# 5_step_seq.net
KiCad netlist of a schematic drawn in Altium Designer
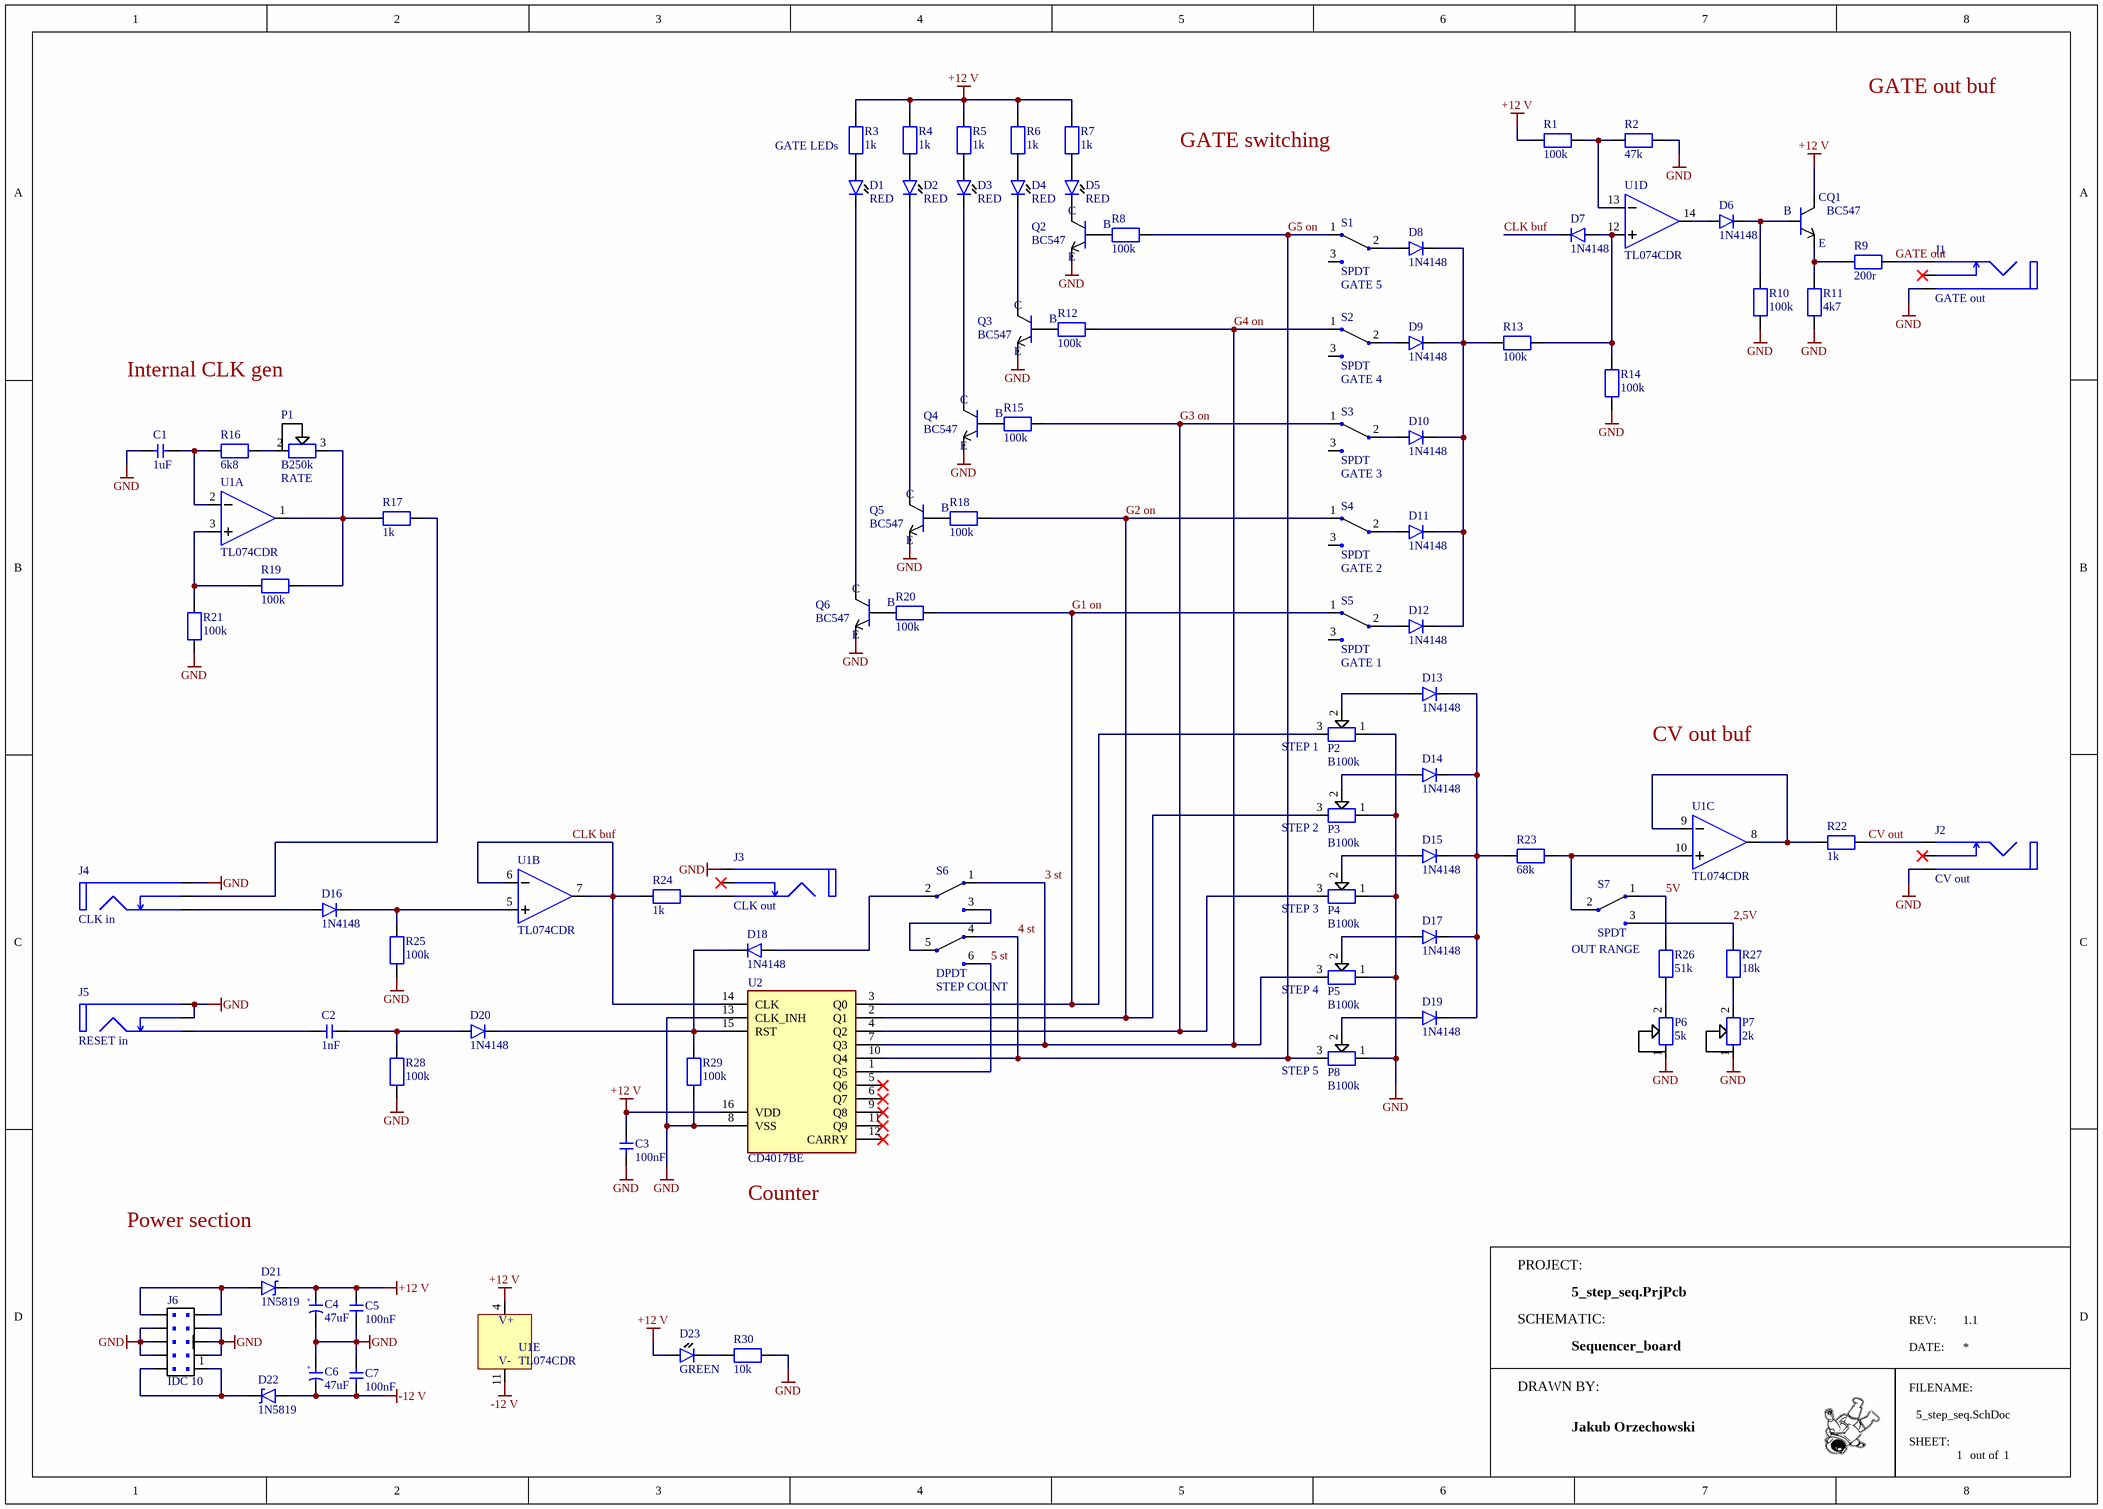
[diagram p0: 5_step_seq.SchDoc]

(export (version "E")
  (design (tool "Eeschema 10.0.6"))
  (components
    (comp (ref "C1")
      (value "1uF")
      (footprint "Cap THT 5mm")
      (description "THT Capacitor Non-Polarised 5 mm Pitch")
      (fields (field (name "Comment") "CAP"))
      (libsource (lib "Generic components") (part "Capacitor THT 5mm"))
    )
    (comp (ref "C2")
      (value "1nF")
      (footprint "Cap THT 5mm")
      (description "THT Capacitor Non-Polarised 5 mm Pitch")
      (fields (field (name "Comment") "CAP"))
      (libsource (lib "Generic components") (part "Capacitor THT 5mm"))
    )
    (comp (ref "C3")
      (value "100nF")
      (footprint "Cap THT 5mm")
      (description "THT Capacitor Non-Polarised 5 mm Pitch")
      (fields (field (name "Comment") "CAP"))
      (libsource (lib "Generic components") (part "Capacitor THT 5mm"))
    )
    (comp (ref "C4")
      (value "47uF")
      (footprint "Cap electrolytic THT 5mm")
      (description "THT Electrolytic Capacitor 5 mm Diameter")
      (fields (field (name "Comment") "CAP"))
      (libsource (lib "Generic components") (part "Capacitor Electr THT 5mm"))
    )
    (comp (ref "C5")
      (value "100nF")
      (footprint "Cap THT 5mm")
      (description "THT Capacitor Non-Polarised 5 mm Pitch")
      (fields (field (name "Comment") "CAP"))
      (libsource (lib "Generic components") (part "Capacitor THT 5mm"))
    )
    (comp (ref "C6")
      (value "47uF")
      (footprint "Cap electrolytic THT 5mm")
      (description "THT Electrolytic Capacitor 5 mm Diameter")
      (fields (field (name "Comment") "CAP"))
      (libsource (lib "Generic components") (part "Capacitor Electr THT 5mm"))
    )
    (comp (ref "C7")
      (value "100nF")
      (footprint "Cap THT 5mm")
      (description "THT Capacitor Non-Polarised 5 mm Pitch")
      (fields (field (name "Comment") "CAP"))
      (libsource (lib "Generic components") (part "Capacitor THT 5mm"))
    )
    (comp (ref "D1")
      (value "LED")
      (footprint "LED THT 5 mm raised")
      (description "THT LED Diode 5 mm Diameter")
      (fields (field (name "COLOR") "RED"))
      (libsource (lib "Opto") (part "LED THT"))
    )
    (comp (ref "D2")
      (value "LED")
      (footprint "LED THT 5 mm raised")
      (description "THT LED Diode 5 mm Diameter")
      (fields (field (name "COLOR") "RED"))
      (libsource (lib "Opto") (part "LED THT"))
    )
    (comp (ref "D3")
      (value "LED")
      (footprint "LED THT 5 mm raised")
      (description "THT LED Diode 5 mm Diameter")
      (fields (field (name "COLOR") "RED"))
      (libsource (lib "Opto") (part "LED THT"))
    )
    (comp (ref "D4")
      (value "LED")
      (footprint "LED THT 5 mm raised")
      (description "THT LED Diode 5 mm Diameter")
      (fields (field (name "COLOR") "RED"))
      (libsource (lib "Opto") (part "LED THT"))
    )
    (comp (ref "D5")
      (value "LED")
      (footprint "LED THT 5 mm raised")
      (description "THT LED Diode 5 mm Diameter")
      (fields (field (name "COLOR") "RED"))
      (libsource (lib "Opto") (part "LED THT"))
    )
    (comp (ref "D6")
      (value "DIODE")
      (footprint "Diode THT 10 mm")
      (description "Generic THT Axial Diode 10 mm Pitch")
      (fields (field (name "MODEL") "1N4148"))
      (libsource (lib "Diodes") (part "Diode THT"))
    )
    (comp (ref "D7")
      (value "DIODE")
      (footprint "Diode THT 10 mm")
      (description "Generic THT Axial Diode 10 mm Pitch")
      (fields (field (name "MODEL") "1N4148"))
      (libsource (lib "Diodes") (part "Diode THT"))
    )
    (comp (ref "D8")
      (value "DIODE")
      (footprint "Diode THT 10 mm")
      (description "Generic THT Axial Diode 10 mm Pitch")
      (fields (field (name "MODEL") "1N4148"))
      (libsource (lib "Diodes") (part "Diode THT"))
    )
    (comp (ref "D9")
      (value "DIODE")
      (footprint "Diode THT 10 mm")
      (description "Generic THT Axial Diode 10 mm Pitch")
      (fields (field (name "MODEL") "1N4148"))
      (libsource (lib "Diodes") (part "Diode THT"))
    )
    (comp (ref "D10")
      (value "DIODE")
      (footprint "Diode THT 10 mm")
      (description "Generic THT Axial Diode 10 mm Pitch")
      (fields (field (name "MODEL") "1N4148"))
      (libsource (lib "Diodes") (part "Diode THT"))
    )
    (comp (ref "D11")
      (value "DIODE")
      (footprint "Diode THT 10 mm")
      (description "Generic THT Axial Diode 10 mm Pitch")
      (fields (field (name "MODEL") "1N4148"))
      (libsource (lib "Diodes") (part "Diode THT"))
    )
    (comp (ref "D12")
      (value "DIODE")
      (footprint "Diode THT 10 mm")
      (description "Generic THT Axial Diode 10 mm Pitch")
      (fields (field (name "MODEL") "1N4148"))
      (libsource (lib "Diodes") (part "Diode THT"))
    )
    (comp (ref "D13")
      (value "DIODE")
      (footprint "Diode THT 10 mm")
      (description "Generic THT Axial Diode 10 mm Pitch")
      (fields (field (name "MODEL") "1N4148"))
      (libsource (lib "Diodes") (part "Diode THT"))
    )
    (comp (ref "D14")
      (value "DIODE")
      (footprint "Diode THT 10 mm")
      (description "Generic THT Axial Diode 10 mm Pitch")
      (fields (field (name "MODEL") "1N4148"))
      (libsource (lib "Diodes") (part "Diode THT"))
    )
    (comp (ref "D15")
      (value "DIODE")
      (footprint "Diode THT 10 mm")
      (description "Generic THT Axial Diode 10 mm Pitch")
      (fields (field (name "MODEL") "1N4148"))
      (libsource (lib "Diodes") (part "Diode THT"))
    )
    (comp (ref "D16")
      (value "DIODE")
      (footprint "Diode THT 10 mm")
      (description "Generic THT Axial Diode 10 mm Pitch")
      (fields (field (name "MODEL") "1N4148"))
      (libsource (lib "Diodes") (part "Diode THT"))
    )
    (comp (ref "D17")
      (value "DIODE")
      (footprint "Diode THT 10 mm")
      (description "Generic THT Axial Diode 10 mm Pitch")
      (fields (field (name "MODEL") "1N4148"))
      (libsource (lib "Diodes") (part "Diode THT"))
    )
    (comp (ref "D18")
      (value "DIODE")
      (footprint "Diode THT 10 mm")
      (description "Generic THT Axial Diode 10 mm Pitch")
      (fields (field (name "MODEL") "1N4148"))
      (libsource (lib "Diodes") (part "Diode THT"))
    )
    (comp (ref "D19")
      (value "DIODE")
      (footprint "Diode THT 10 mm")
      (description "Generic THT Axial Diode 10 mm Pitch")
      (fields (field (name "MODEL") "1N4148"))
      (libsource (lib "Diodes") (part "Diode THT"))
    )
    (comp (ref "D20")
      (value "DIODE")
      (footprint "Diode THT 10 mm")
      (description "Generic THT Axial Diode 10 mm Pitch")
      (fields (field (name "MODEL") "1N4148"))
      (libsource (lib "Diodes") (part "Diode THT"))
    )
    (comp (ref "D21")
      (value "SCHOTTKY")
      (footprint "Diode THT 10 mm")
      (description "Generic THT Axial Schottky Diode 10 mm Pitch")
      (fields (field (name "MODEL") "1N5819"))
      (libsource (lib "Diodes") (part "Schottky Diode THT"))
    )
    (comp (ref "D22")
      (value "SCHOTTKY")
      (footprint "Diode THT 10 mm")
      (description "Generic THT Axial Schottky Diode 10 mm Pitch")
      (fields (field (name "MODEL") "1N5819"))
      (libsource (lib "Diodes") (part "Schottky Diode THT"))
    )
    (comp (ref "D23")
      (value "LED")
      (footprint "LED SMD 0805")
      (description "SMD LED Diode 0805 Package")
      (fields (field (name "COLOR") "GREEN"))
      (libsource (lib "Opto") (part "LED SMD"))
    )
    (comp (ref "J1")
      (value "JACK Mono")
      (footprint "PJ301M")
      (description "PJ301M Eurorack 3,5 mm Patch Socket PCB Mount")
      (fields (field (name "LABEL") "GATE out"))
      (libsource (lib "Connectors") (part "PJ301M"))
    )
    (comp (ref "J2")
      (value "JACK Mono")
      (footprint "PJ301M")
      (description "PJ301M Eurorack 3,5 mm Patch Socket PCB Mount")
      (fields (field (name "LABEL") "CV out"))
      (libsource (lib "Connectors") (part "PJ301M"))
    )
    (comp (ref "J3")
      (value "JACK Mono")
      (footprint "PJ301M")
      (description "PJ301M Eurorack 3,5 mm Patch Socket PCB Mount")
      (fields (field (name "LABEL") "CLK out"))
      (libsource (lib "Connectors") (part "PJ301M"))
    )
    (comp (ref "J4")
      (value "JACK Mono")
      (footprint "PJ301M")
      (description "PJ301M Eurorack 3,5 mm Patch Socket PCB Mount")
      (fields (field (name "LABEL") "CLK in"))
      (libsource (lib "Connectors") (part "PJ301M"))
    )
    (comp (ref "J5")
      (value "JACK Mono")
      (footprint "PJ301M")
      (description "PJ301M Eurorack 3,5 mm Patch Socket PCB Mount")
      (fields (field (name "LABEL") "RESET in"))
      (libsource (lib "Connectors") (part "PJ301M"))
    )
    (comp (ref "J6")
      (value "IDC 10")
      (footprint "IDC 10 PIN")
      (description "10 Pin IDC Connector")
      (libsource (lib "Connectors") (part "IDC 10 pin"))
    )
    (comp (ref "P1")
      (value "B250k")
      (footprint "9 mm PCB Potentiometer")
      (description "PCB Mount 9mm Mono Potentiometer THT as Variable Resistor Clockwise Decrease")
      (fields (field (name "PARAMETER") "RATE") (field (name "Comment") "VR"))
      (libsource (lib "Potentiometers") (part "VR B 9 mm"))
    )
    (comp (ref "P2")
      (value "B100k")
      (footprint "9 mm PCB Potentiometer")
      (description "PCB Mount 9mm Mono Potentiometer THT")
      (fields (field (name "PARAMETER") "STEP 1") (field (name "Comment") "Mono Pot"))
      (libsource (lib "Potentiometers") (part "Potentiometer 9 mm"))
    )
    (comp (ref "P3")
      (value "B100k")
      (footprint "9 mm PCB Potentiometer")
      (description "PCB Mount 9mm Mono Potentiometer THT")
      (fields (field (name "PARAMETER") "STEP 2") (field (name "Comment") "Mono Pot"))
      (libsource (lib "Potentiometers") (part "Potentiometer 9 mm"))
    )
    (comp (ref "P4")
      (value "B100k")
      (footprint "9 mm PCB Potentiometer")
      (description "PCB Mount 9mm Mono Potentiometer THT")
      (fields (field (name "PARAMETER") "STEP 3") (field (name "Comment") "Mono Pot"))
      (libsource (lib "Potentiometers") (part "Potentiometer 9 mm"))
    )
    (comp (ref "P5")
      (value "B100k")
      (footprint "9 mm PCB Potentiometer")
      (description "PCB Mount 9mm Mono Potentiometer THT")
      (fields (field (name "PARAMETER") "STEP 4") (field (name "Comment") "Mono Pot"))
      (libsource (lib "Potentiometers") (part "Potentiometer 9 mm"))
    )
    (comp (ref "P6")
      (value "5k")
      (footprint "Multiturn Potentiometer inline")
      (description "PCB Mount Multiturn Trimmer Potentiometer Top Adjustable as Variable Resistor Clockwise Increase")
      (fields (field (name "Comment") "VR"))
      (libsource (lib "Potentiometers") (part "VR A Multiturn THT"))
    )
    (comp (ref "P7")
      (value "2k")
      (footprint "Multiturn Potentiometer inline")
      (description "PCB Mount Multiturn Trimmer Potentiometer Top Adjustable as Variable Resistor Clockwise Increase")
      (fields (field (name "Comment") "VR"))
      (libsource (lib "Potentiometers") (part "VR A Multiturn THT"))
    )
    (comp (ref "P8")
      (value "B100k")
      (footprint "9 mm PCB Potentiometer")
      (description "PCB Mount 9mm Mono Potentiometer THT")
      (fields (field (name "PARAMETER") "STEP 5") (field (name "Comment") "Mono Pot"))
      (libsource (lib "Potentiometers") (part "Potentiometer 9 mm"))
    )
    (comp (ref "Q1")
      (value "BC547")
      (footprint "TO-92 wide")
      (description "BC547 NPN Transistor THT TO-92 Package")
      (libsource (lib "Transistors") (part "BC547"))
    )
    (comp (ref "Q2")
      (value "BC547")
      (footprint "TO-92 wide")
      (description "BC547 NPN Transistor THT TO-92 Package")
      (libsource (lib "Transistors") (part "BC547"))
    )
    (comp (ref "Q3")
      (value "BC547")
      (footprint "TO-92 wide")
      (description "BC547 NPN Transistor THT TO-92 Package")
      (libsource (lib "Transistors") (part "BC547"))
    )
    (comp (ref "Q4")
      (value "BC547")
      (footprint "TO-92 wide")
      (description "BC547 NPN Transistor THT TO-92 Package")
      (libsource (lib "Transistors") (part "BC547"))
    )
    (comp (ref "Q5")
      (value "BC547")
      (footprint "TO-92 wide")
      (description "BC547 NPN Transistor THT TO-92 Package")
      (libsource (lib "Transistors") (part "BC547"))
    )
    (comp (ref "Q6")
      (value "BC547")
      (footprint "TO-92 wide")
      (description "BC547 NPN Transistor THT TO-92 Package")
      (libsource (lib "Transistors") (part "BC547"))
    )
    (comp (ref "R1")
      (value "100k")
      (footprint "Resistor THT vertical")
      (description "THT Axial Resistor 10mm Pitch")
      (fields (field (name "Comment") "RES"))
      (libsource (lib "Generic components") (part "Resistor THT"))
    )
    (comp (ref "R2")
      (value "47k")
      (footprint "Resistor THT vertical")
      (description "THT Axial Resistor 10mm Pitch")
      (fields (field (name "Comment") "RES"))
      (libsource (lib "Generic components") (part "Resistor THT"))
    )
    (comp (ref "R3")
      (value "1k")
      (footprint "Resistor THT vertical")
      (description "THT Axial Resistor 10mm Pitch")
      (fields (field (name "Comment") "RES"))
      (libsource (lib "Generic components") (part "Resistor THT"))
    )
    (comp (ref "R4")
      (value "1k")
      (footprint "Resistor THT vertical")
      (description "THT Axial Resistor 10mm Pitch")
      (fields (field (name "Comment") "RES"))
      (libsource (lib "Generic components") (part "Resistor THT"))
    )
    (comp (ref "R5")
      (value "1k")
      (footprint "Resistor THT vertical")
      (description "THT Axial Resistor 10mm Pitch")
      (fields (field (name "Comment") "RES"))
      (libsource (lib "Generic components") (part "Resistor THT"))
    )
    (comp (ref "R6")
      (value "1k")
      (footprint "Resistor THT vertical")
      (description "THT Axial Resistor 10mm Pitch")
      (fields (field (name "Comment") "RES"))
      (libsource (lib "Generic components") (part "Resistor THT"))
    )
    (comp (ref "R7")
      (value "1k")
      (footprint "Resistor THT vertical")
      (description "THT Axial Resistor 10mm Pitch")
      (fields (field (name "Comment") "RES"))
      (libsource (lib "Generic components") (part "Resistor THT"))
    )
    (comp (ref "R8")
      (value "100k")
      (footprint "Resistor THT 10mm")
      (description "THT Axial Resistor 10mm Pitch")
      (fields (field (name "Comment") "RES"))
      (libsource (lib "Generic components") (part "Resistor THT"))
    )
    (comp (ref "R9")
      (value "200r")
      (footprint "Resistor THT vertical")
      (description "THT Axial Resistor 10mm Pitch")
      (fields (field (name "Comment") "RES"))
      (libsource (lib "Generic components") (part "Resistor THT"))
    )
    (comp (ref "R10")
      (value "100k")
      (footprint "Resistor THT vertical")
      (description "THT Axial Resistor 10mm Pitch")
      (fields (field (name "Comment") "RES"))
      (libsource (lib "Generic components") (part "Resistor THT"))
    )
    (comp (ref "R11")
      (value "4k7")
      (footprint "Resistor THT vertical")
      (description "THT Axial Resistor 10mm Pitch")
      (fields (field (name "Comment") "RES"))
      (libsource (lib "Generic components") (part "Resistor THT"))
    )
    (comp (ref "R12")
      (value "100k")
      (footprint "Resistor THT 10mm")
      (description "THT Axial Resistor 10mm Pitch")
      (fields (field (name "Comment") "RES"))
      (libsource (lib "Generic components") (part "Resistor THT"))
    )
    (comp (ref "R13")
      (value "100k")
      (footprint "Resistor THT vertical")
      (description "THT Axial Resistor 10mm Pitch")
      (fields (field (name "Comment") "RES"))
      (libsource (lib "Generic components") (part "Resistor THT"))
    )
    (comp (ref "R14")
      (value "100k")
      (footprint "Resistor THT vertical")
      (description "THT Axial Resistor 10mm Pitch")
      (fields (field (name "Comment") "RES"))
      (libsource (lib "Generic components") (part "Resistor THT"))
    )
    (comp (ref "R15")
      (value "100k")
      (footprint "Resistor THT 10mm")
      (description "THT Axial Resistor 10mm Pitch")
      (fields (field (name "Comment") "RES"))
      (libsource (lib "Generic components") (part "Resistor THT"))
    )
    (comp (ref "R16")
      (value "6k8")
      (footprint "Resistor THT 10mm")
      (description "THT Axial Resistor 10mm Pitch")
      (fields (field (name "Comment") "RES"))
      (libsource (lib "Generic components") (part "Resistor THT"))
    )
    (comp (ref "R17")
      (value "1k")
      (footprint "Resistor THT 10mm")
      (description "THT Axial Resistor 10mm Pitch")
      (fields (field (name "Comment") "RES"))
      (libsource (lib "Generic components") (part "Resistor THT"))
    )
    (comp (ref "R18")
      (value "100k")
      (footprint "Resistor THT 10mm")
      (description "THT Axial Resistor 10mm Pitch")
      (fields (field (name "Comment") "RES"))
      (libsource (lib "Generic components") (part "Resistor THT"))
    )
    (comp (ref "R19")
      (value "100k")
      (footprint "Resistor THT 10mm")
      (description "THT Axial Resistor 10mm Pitch")
      (fields (field (name "Comment") "RES"))
      (libsource (lib "Generic components") (part "Resistor THT"))
    )
    (comp (ref "R20")
      (value "100k")
      (footprint "Resistor THT 10mm")
      (description "THT Axial Resistor 10mm Pitch")
      (fields (field (name "Comment") "RES"))
      (libsource (lib "Generic components") (part "Resistor THT"))
    )
    (comp (ref "R21")
      (value "100k")
      (footprint "Resistor THT 10mm")
      (description "THT Axial Resistor 10mm Pitch")
      (fields (field (name "Comment") "RES"))
      (libsource (lib "Generic components") (part "Resistor THT"))
    )
    (comp (ref "R22")
      (value "1k")
      (footprint "Resistor THT 10mm")
      (description "THT Axial Resistor 10mm Pitch")
      (fields (field (name "Comment") "RES"))
      (libsource (lib "Generic components") (part "Resistor THT"))
    )
    (comp (ref "R23")
      (value "68k")
      (footprint "Resistor THT 10mm")
      (description "THT Axial Resistor 10mm Pitch")
      (fields (field (name "Comment") "RES"))
      (libsource (lib "Generic components") (part "Resistor THT"))
    )
    (comp (ref "R24")
      (value "1k")
      (footprint "Resistor THT vertical")
      (description "THT Axial Resistor 10mm Pitch")
      (fields (field (name "Comment") "RES"))
      (libsource (lib "Generic components") (part "Resistor THT"))
    )
    (comp (ref "R25")
      (value "100k")
      (footprint "Resistor THT 10mm")
      (description "THT Axial Resistor 10mm Pitch")
      (fields (field (name "Comment") "RES"))
      (libsource (lib "Generic components") (part "Resistor THT"))
    )
    (comp (ref "R26")
      (value "51k")
      (footprint "Resistor THT vertical")
      (description "THT Axial Resistor 10mm Pitch")
      (fields (field (name "Comment") "RES"))
      (libsource (lib "Generic components") (part "Resistor THT"))
    )
    (comp (ref "R27")
      (value "18k")
      (footprint "Resistor THT vertical")
      (description "THT Axial Resistor 10mm Pitch")
      (fields (field (name "Comment") "RES"))
      (libsource (lib "Generic components") (part "Resistor THT"))
    )
    (comp (ref "R28")
      (value "100k")
      (footprint "Resistor THT 10mm")
      (description "THT Axial Resistor 10mm Pitch")
      (fields (field (name "Comment") "RES"))
      (libsource (lib "Generic components") (part "Resistor THT"))
    )
    (comp (ref "R29")
      (value "100k")
      (footprint "Resistor THT 10mm")
      (description "THT Axial Resistor 10mm Pitch")
      (fields (field (name "Comment") "RES"))
      (libsource (lib "Generic components") (part "Resistor THT"))
    )
    (comp (ref "R30")
      (value "10k")
      (footprint "Resistor SMD 0805")
      (description "SMD Resistor 0805 package")
      (fields (field (name "Comment") "RES"))
      (libsource (lib "Generic components") (part "Resistor SMD 0805"))
    )
    (comp (ref "S1")
      (value "SPDT")
      (footprint "2MS1T1B5M2RE")
      (description "Single Pole Double Throw on-on Switch")
      (fields (field (name "SIGNALS") "GATE 5"))
      (libsource (lib "Switches") (part "2MS1T1B5M2RE SPDT (Eurorack)"))
    )
    (comp (ref "S2")
      (value "SPDT")
      (footprint "2MS1T1B5M2RE")
      (description "Single Pole Double Throw on-on Switch")
      (fields (field (name "SIGNALS") "GATE 4"))
      (libsource (lib "Switches") (part "2MS1T1B5M2RE SPDT (Eurorack)"))
    )
    (comp (ref "S3")
      (value "SPDT")
      (footprint "2MS1T1B5M2RE")
      (description "Single Pole Double Throw on-on Switch")
      (fields (field (name "SIGNALS") "GATE 3"))
      (libsource (lib "Switches") (part "2MS1T1B5M2RE SPDT (Eurorack)"))
    )
    (comp (ref "S4")
      (value "SPDT")
      (footprint "2MS1T1B5M2RE")
      (description "Single Pole Double Throw on-on Switch")
      (fields (field (name "SIGNALS") "GATE 2"))
      (libsource (lib "Switches") (part "2MS1T1B5M2RE SPDT (Eurorack)"))
    )
    (comp (ref "S5")
      (value "SPDT")
      (footprint "2MS1T1B5M2RE")
      (description "Single Pole Double Throw on-on Switch")
      (fields (field (name "SIGNALS") "GATE 1"))
      (libsource (lib "Switches") (part "2MS1T1B5M2RE SPDT (Eurorack)"))
    )
    (comp (ref "S6")
      (value "DPDT")
      (footprint "2MD6T1B5M2RE")
      (description "Dual Pole Dual Throw on-on-on Switch")
      (fields (field (name "SIGNALS") "STEP COUNT"))
      (libsource (lib "Switches") (part "2MD6T1B5M2RE DPDT (Eurorack)"))
    )
    (comp (ref "S7")
      (value "SPDT")
      (footprint "2MS1T1B5M2RE")
      (description "Single Pole Double Throw on-on Switch")
      (fields (field (name "SIGNALS") "OUT RANGE"))
      (libsource (lib "Switches") (part "2MS1T1B5M2RE SPDT (Eurorack)"))
    )
    (comp (ref "U1")
      (value "TL074CDR")
      (footprint "SOIC14")
      (description "TL074CDR Quad Op-Amp SOIC14 Package")
      (libsource (lib "OpAmps") (part "TL074CDR SOIC14"))
    )
    (comp (ref "U2")
      (value "CD4017BE")
      (footprint "DIP-16 socket")
      (description "CD4017BE CMOS Decade Counter DIP-16 Package")
      (libsource (lib "ICs") (part "CD4017BE DIP-16"))
    )
  )
  (nets
    (net (code "1") (name "+12 V") (class "Default")
      (node (ref "C3") (pin "2") (pintype "passive"))
      (node (ref "C4") (pin "2") (pintype "passive"))
      (node (ref "C5") (pin "2") (pintype "passive"))
      (node (ref "D21") (pin "2") (pintype "passive"))
      (node (ref "D23") (pin "1") (pintype "passive"))
      (node (ref "Q1") (pin "1") (pintype "passive"))
      (node (ref "R1") (pin "1") (pintype "passive"))
      (node (ref "R3") (pin "2") (pintype "passive"))
      (node (ref "R4") (pin "2") (pintype "passive"))
      (node (ref "R5") (pin "2") (pintype "passive"))
      (node (ref "R6") (pin "2") (pintype "passive"))
      (node (ref "R7") (pin "2") (pintype "passive"))
      (node (ref "U1") (pin "4") (pintype "passive"))
      (node (ref "U2") (pin "16") (pinfunction "VDD_16") (pintype "passive"))
    )
    (net (code "2") (name "-12 V") (class "Default")
      (node (ref "C6") (pin "1") (pintype "passive"))
      (node (ref "C7") (pin "1") (pintype "passive"))
      (node (ref "D22") (pin "1") (pintype "passive"))
      (node (ref "U1") (pin "11") (pintype "passive"))
    )
    (net (code "3") (name "/2,5V") (class "Default")
      (node (ref "R27") (pin "1") (pintype "passive"))
      (node (ref "S7") (pin "3") (pintype "passive"))
    )
    (net (code "4") (name "/3 st") (class "Default")
      (node (ref "P5") (pin "3") (pintype "passive"))
      (node (ref "R12") (pin "2") (pintype "passive"))
      (node (ref "S2") (pin "1") (pintype "passive"))
      (node (ref "S6") (pin "1") (pintype "passive"))
      (node (ref "U2") (pin "7") (pinfunction "Q3_7") (pintype "passive"))
    )
    (net (code "5") (name "/4 st") (class "Default")
      (node (ref "P8") (pin "3") (pintype "passive"))
      (node (ref "R8") (pin "2") (pintype "passive"))
      (node (ref "S1") (pin "1") (pintype "passive"))
      (node (ref "S6") (pin "4") (pintype "passive"))
      (node (ref "U2") (pin "10") (pinfunction "Q4_10") (pintype "passive"))
    )
    (net (code "6") (name "/5 st") (class "Default")
      (node (ref "S6") (pin "6") (pintype "passive"))
      (node (ref "U2") (pin "1") (pinfunction "Q5_1") (pintype "passive"))
    )
    (net (code "7") (name "/5V") (class "Default")
      (node (ref "R26") (pin "1") (pintype "passive"))
      (node (ref "S7") (pin "1") (pintype "passive"))
    )
    (net (code "8") (name "/CLK buf") (class "Default")
      (node (ref "D7") (pin "2") (pintype "passive"))
      (node (ref "R24") (pin "2") (pintype "passive"))
      (node (ref "U1") (pin "6") (pintype "passive"))
      (node (ref "U1") (pin "7") (pintype "passive"))
      (node (ref "U2") (pin "14") (pinfunction "CLK_14") (pintype "passive"))
    )
    (net (code "9") (name "/CV out") (class "Default")
      (node (ref "J2") (pin "3") (pintype "passive"))
      (node (ref "R22") (pin "1") (pintype "passive"))
    )
    (net (code "10") (name "/G1 on") (class "Default")
      (node (ref "P2") (pin "3") (pintype "passive"))
      (node (ref "R20") (pin "2") (pintype "passive"))
      (node (ref "S5") (pin "1") (pintype "passive"))
      (node (ref "U2") (pin "3") (pinfunction "Q0_3") (pintype "passive"))
    )
    (net (code "11") (name "/G2 on") (class "Default")
      (node (ref "P3") (pin "3") (pintype "passive"))
      (node (ref "R18") (pin "2") (pintype "passive"))
      (node (ref "S4") (pin "1") (pintype "passive"))
      (node (ref "U2") (pin "2") (pinfunction "Q1_2") (pintype "passive"))
    )
    (net (code "12") (name "/G3 on") (class "Default")
      (node (ref "P4") (pin "3") (pintype "passive"))
      (node (ref "R15") (pin "2") (pintype "passive"))
      (node (ref "S3") (pin "1") (pintype "passive"))
      (node (ref "U2") (pin "4") (pinfunction "Q2_4") (pintype "passive"))
    )
    (net (code "13") (name "/GATE out") (class "Default")
      (node (ref "J1") (pin "3") (pintype "passive"))
      (node (ref "R9") (pin "1") (pintype "passive"))
    )
    (net (code "14") (name "GND") (class "Default")
      (node (ref "C1") (pin "1") (pintype "passive"))
      (node (ref "C3") (pin "1") (pintype "passive"))
      (node (ref "C4") (pin "1") (pintype "passive"))
      (node (ref "C5") (pin "1") (pintype "passive"))
      (node (ref "C6") (pin "2") (pintype "passive"))
      (node (ref "C7") (pin "2") (pintype "passive"))
      (node (ref "J1") (pin "1") (pintype "passive"))
      (node (ref "J2") (pin "1") (pintype "passive"))
      (node (ref "J3") (pin "1") (pintype "passive"))
      (node (ref "J4") (pin "1") (pintype "passive"))
      (node (ref "J5") (pin "1") (pintype "passive"))
      (node (ref "J5") (pin "2") (pintype "passive"))
      (node (ref "J6") (pin "3") (pintype "passive"))
      (node (ref "J6") (pin "4") (pintype "passive"))
      (node (ref "J6") (pin "5") (pintype "passive"))
      (node (ref "J6") (pin "6") (pintype "passive"))
      (node (ref "J6") (pin "7") (pintype "passive"))
      (node (ref "J6") (pin "8") (pintype "passive"))
      (node (ref "P2") (pin "1") (pintype "passive"))
      (node (ref "P3") (pin "1") (pintype "passive"))
      (node (ref "P4") (pin "1") (pintype "passive"))
      (node (ref "P5") (pin "1") (pintype "passive"))
      (node (ref "P6") (pin "1") (pintype "passive"))
      (node (ref "P7") (pin "1") (pintype "passive"))
      (node (ref "P8") (pin "1") (pintype "passive"))
      (node (ref "Q2") (pin "3") (pintype "passive"))
      (node (ref "Q3") (pin "3") (pintype "passive"))
      (node (ref "Q4") (pin "3") (pintype "passive"))
      (node (ref "Q5") (pin "3") (pintype "passive"))
      (node (ref "Q6") (pin "3") (pintype "passive"))
      (node (ref "R10") (pin "2") (pintype "passive"))
      (node (ref "R11") (pin "2") (pintype "passive"))
      (node (ref "R14") (pin "1") (pintype "passive"))
      (node (ref "R2") (pin "2") (pintype "passive"))
      (node (ref "R21") (pin "1") (pintype "passive"))
      (node (ref "R25") (pin "1") (pintype "passive"))
      (node (ref "R28") (pin "1") (pintype "passive"))
      (node (ref "R29") (pin "1") (pintype "passive"))
      (node (ref "R30") (pin "2") (pintype "passive"))
      (node (ref "U2") (pin "13") (pinfunction "CLK_INH_13") (pintype "passive"))
      (node (ref "U2") (pin "8") (pinfunction "VSS_8") (pintype "passive"))
    )
    (net (code "15") (name "Net-(C1-Pad2)") (class "Default")
      (node (ref "C1") (pin "2") (pintype "passive"))
      (node (ref "R16") (pin "1") (pintype "passive"))
      (node (ref "U1") (pin "2") (pintype "passive"))
    )
    (net (code "16") (name "Net-(C2-Pad1)") (class "Default")
      (node (ref "C2") (pin "1") (pintype "passive"))
      (node (ref "J5") (pin "3") (pintype "passive"))
    )
    (net (code "17") (name "Net-(C2-Pad2)") (class "Default")
      (node (ref "C2") (pin "2") (pintype "passive"))
      (node (ref "D20") (pin "1") (pintype "passive"))
      (node (ref "R28") (pin "2") (pintype "passive"))
    )
    (net (code "18") (name "Net-(D1-Pad1)") (class "Default")
      (node (ref "D1") (pin "1") (pintype "passive"))
      (node (ref "R3") (pin "1") (pintype "passive"))
    )
    (net (code "19") (name "Net-(D1-Pad2)") (class "Default")
      (node (ref "D1") (pin "2") (pintype "passive"))
      (node (ref "Q6") (pin "1") (pintype "passive"))
    )
    (net (code "20") (name "Net-(D2-Pad1)") (class "Default")
      (node (ref "D2") (pin "1") (pintype "passive"))
      (node (ref "R4") (pin "1") (pintype "passive"))
    )
    (net (code "21") (name "Net-(D2-Pad2)") (class "Default")
      (node (ref "D2") (pin "2") (pintype "passive"))
      (node (ref "Q5") (pin "1") (pintype "passive"))
    )
    (net (code "22") (name "Net-(D3-Pad1)") (class "Default")
      (node (ref "D3") (pin "1") (pintype "passive"))
      (node (ref "R5") (pin "1") (pintype "passive"))
    )
    (net (code "23") (name "Net-(D3-Pad2)") (class "Default")
      (node (ref "D3") (pin "2") (pintype "passive"))
      (node (ref "Q4") (pin "1") (pintype "passive"))
    )
    (net (code "24") (name "Net-(D4-Pad1)") (class "Default")
      (node (ref "D4") (pin "1") (pintype "passive"))
      (node (ref "R6") (pin "1") (pintype "passive"))
    )
    (net (code "25") (name "Net-(D4-Pad2)") (class "Default")
      (node (ref "D4") (pin "2") (pintype "passive"))
      (node (ref "Q3") (pin "1") (pintype "passive"))
    )
    (net (code "26") (name "Net-(D5-Pad1)") (class "Default")
      (node (ref "D5") (pin "1") (pintype "passive"))
      (node (ref "R7") (pin "1") (pintype "passive"))
    )
    (net (code "27") (name "Net-(D5-Pad2)") (class "Default")
      (node (ref "D5") (pin "2") (pintype "passive"))
      (node (ref "Q2") (pin "1") (pintype "passive"))
    )
    (net (code "28") (name "Net-(D6-Pad1)") (class "Default")
      (node (ref "D6") (pin "1") (pintype "passive"))
      (node (ref "U1") (pin "14") (pintype "passive"))
    )
    (net (code "29") (name "Net-(D6-Pad2)") (class "Default")
      (node (ref "D6") (pin "2") (pintype "passive"))
      (node (ref "Q1") (pin "2") (pintype "passive"))
      (node (ref "R10") (pin "1") (pintype "passive"))
    )
    (net (code "30") (name "Net-(D7-Pad1)") (class "Default")
      (node (ref "D7") (pin "1") (pintype "passive"))
      (node (ref "R13") (pin "2") (pintype "passive"))
      (node (ref "R14") (pin "2") (pintype "passive"))
      (node (ref "U1") (pin "12") (pintype "passive"))
    )
    (net (code "31") (name "Net-(D8-Pad1)") (class "Default")
      (node (ref "D8") (pin "1") (pintype "passive"))
      (node (ref "S1") (pin "2") (pintype "passive"))
    )
    (net (code "32") (name "Net-(D9-Pad1)") (class "Default")
      (node (ref "D9") (pin "1") (pintype "passive"))
      (node (ref "S2") (pin "2") (pintype "passive"))
    )
    (net (code "33") (name "Net-(D10-Pad1)") (class "Default")
      (node (ref "D10") (pin "1") (pintype "passive"))
      (node (ref "S3") (pin "2") (pintype "passive"))
    )
    (net (code "34") (name "Net-(D10-Pad2)") (class "Default")
      (node (ref "D10") (pin "2") (pintype "passive"))
      (node (ref "D11") (pin "2") (pintype "passive"))
      (node (ref "D12") (pin "2") (pintype "passive"))
      (node (ref "D8") (pin "2") (pintype "passive"))
      (node (ref "D9") (pin "2") (pintype "passive"))
      (node (ref "R13") (pin "1") (pintype "passive"))
    )
    (net (code "35") (name "Net-(D11-Pad1)") (class "Default")
      (node (ref "D11") (pin "1") (pintype "passive"))
      (node (ref "S4") (pin "2") (pintype "passive"))
    )
    (net (code "36") (name "Net-(D12-Pad1)") (class "Default")
      (node (ref "D12") (pin "1") (pintype "passive"))
      (node (ref "S5") (pin "2") (pintype "passive"))
    )
    (net (code "37") (name "Net-(D13-Pad1)") (class "Default")
      (node (ref "D13") (pin "1") (pintype "passive"))
      (node (ref "P2") (pin "2") (pintype "passive"))
    )
    (net (code "38") (name "Net-(D13-Pad2)") (class "Default")
      (node (ref "D13") (pin "2") (pintype "passive"))
      (node (ref "D14") (pin "2") (pintype "passive"))
      (node (ref "D15") (pin "2") (pintype "passive"))
      (node (ref "D17") (pin "2") (pintype "passive"))
      (node (ref "D19") (pin "2") (pintype "passive"))
      (node (ref "R23") (pin "2") (pintype "passive"))
    )
    (net (code "39") (name "Net-(D14-Pad1)") (class "Default")
      (node (ref "D14") (pin "1") (pintype "passive"))
      (node (ref "P3") (pin "2") (pintype "passive"))
    )
    (net (code "40") (name "Net-(D15-Pad1)") (class "Default")
      (node (ref "D15") (pin "1") (pintype "passive"))
      (node (ref "P4") (pin "2") (pintype "passive"))
    )
    (net (code "41") (name "Net-(D16-Pad1)") (class "Default")
      (node (ref "D16") (pin "1") (pintype "passive"))
      (node (ref "J4") (pin "3") (pintype "passive"))
    )
    (net (code "42") (name "Net-(D16-Pad2)") (class "Default")
      (node (ref "D16") (pin "2") (pintype "passive"))
      (node (ref "R25") (pin "2") (pintype "passive"))
      (node (ref "U1") (pin "5") (pintype "passive"))
    )
    (net (code "43") (name "Net-(D17-Pad1)") (class "Default")
      (node (ref "D17") (pin "1") (pintype "passive"))
      (node (ref "P5") (pin "2") (pintype "passive"))
    )
    (net (code "44") (name "Net-(D18-Pad1)") (class "Default")
      (node (ref "D18") (pin "1") (pintype "passive"))
      (node (ref "S6") (pin "2") (pintype "passive"))
    )
    (net (code "45") (name "Net-(D19-Pad1)") (class "Default")
      (node (ref "D19") (pin "1") (pintype "passive"))
      (node (ref "P8") (pin "2") (pintype "passive"))
    )
    (net (code "46") (name "Net-(D21-Pad1)") (class "Default")
      (node (ref "D21") (pin "1") (pintype "passive"))
      (node (ref "J6") (pin "10") (pintype "passive"))
      (node (ref "J6") (pin "9") (pintype "passive"))
    )
    (net (code "47") (name "Net-(D22-Pad2)") (class "Default")
      (node (ref "D22") (pin "2") (pintype "passive"))
      (node (ref "J6") (pin "1") (pintype "passive"))
      (node (ref "J6") (pin "2") (pintype "passive"))
    )
    (net (code "48") (name "Net-(D23-Pad2)") (class "Default")
      (node (ref "D23") (pin "2") (pintype "passive"))
      (node (ref "R30") (pin "1") (pintype "passive"))
    )
    (net (code "49") (name "Net-(J3-Pad3)") (class "Default")
      (node (ref "J3") (pin "3") (pintype "passive"))
      (node (ref "R24") (pin "1") (pintype "passive"))
    )
    (net (code "50") (name "Net-(J4-Pad2)") (class "Default")
      (node (ref "J4") (pin "2") (pintype "passive"))
      (node (ref "R17") (pin "2") (pintype "passive"))
    )
    (net (code "51") (name "Net-(P1-Pad2)") (class "Default")
      (node (ref "P1") (pin "2") (pintype "passive"))
      (node (ref "R16") (pin "2") (pintype "passive"))
    )
    (net (code "52") (name "Net-(P1-Pad3)") (class "Default")
      (node (ref "P1") (pin "3") (pintype "passive"))
      (node (ref "R17") (pin "1") (pintype "passive"))
      (node (ref "R19") (pin "2") (pintype "passive"))
      (node (ref "U1") (pin "1") (pintype "passive"))
    )
    (net (code "53") (name "Net-(P6-Pad2)") (class "Default")
      (node (ref "P6") (pin "2") (pintype "passive"))
      (node (ref "R26") (pin "2") (pintype "passive"))
    )
    (net (code "54") (name "Net-(P7-Pad2)") (class "Default")
      (node (ref "P7") (pin "2") (pintype "passive"))
      (node (ref "R27") (pin "2") (pintype "passive"))
    )
    (net (code "55") (name "Net-(Q1-Pad3)") (class "Default")
      (node (ref "Q1") (pin "3") (pintype "passive"))
      (node (ref "R11") (pin "1") (pintype "passive"))
      (node (ref "R9") (pin "2") (pintype "passive"))
    )
    (net (code "56") (name "Net-(Q2-Pad2)") (class "Default")
      (node (ref "Q2") (pin "2") (pintype "passive"))
      (node (ref "R8") (pin "1") (pintype "passive"))
    )
    (net (code "57") (name "Net-(Q3-Pad2)") (class "Default")
      (node (ref "Q3") (pin "2") (pintype "passive"))
      (node (ref "R12") (pin "1") (pintype "passive"))
    )
    (net (code "58") (name "Net-(Q4-Pad2)") (class "Default")
      (node (ref "Q4") (pin "2") (pintype "passive"))
      (node (ref "R15") (pin "1") (pintype "passive"))
    )
    (net (code "59") (name "Net-(Q5-Pad2)") (class "Default")
      (node (ref "Q5") (pin "2") (pintype "passive"))
      (node (ref "R18") (pin "1") (pintype "passive"))
    )
    (net (code "60") (name "Net-(Q6-Pad2)") (class "Default")
      (node (ref "Q6") (pin "2") (pintype "passive"))
      (node (ref "R20") (pin "1") (pintype "passive"))
    )
    (net (code "61") (name "Net-(R1-Pad2)") (class "Default")
      (node (ref "R1") (pin "2") (pintype "passive"))
      (node (ref "R2") (pin "1") (pintype "passive"))
      (node (ref "U1") (pin "13") (pintype "passive"))
    )
    (net (code "62") (name "Net-(R19-Pad1)") (class "Default")
      (node (ref "R19") (pin "1") (pintype "passive"))
      (node (ref "R21") (pin "2") (pintype "passive"))
      (node (ref "U1") (pin "3") (pintype "passive"))
    )
    (net (code "63") (name "Net-(R22-Pad2)") (class "Default")
      (node (ref "R22") (pin "2") (pintype "passive"))
      (node (ref "U1") (pin "8") (pintype "passive"))
      (node (ref "U1") (pin "9") (pintype "passive"))
    )
    (net (code "64") (name "Net-(R23-Pad1)") (class "Default")
      (node (ref "R23") (pin "1") (pintype "passive"))
      (node (ref "S7") (pin "2") (pintype "passive"))
      (node (ref "U1") (pin "10") (pintype "passive"))
    )
    (net (code "65") (name "Net-(S6-Pad3)") (class "Default")
      (node (ref "S6") (pin "3") (pintype "passive"))
      (node (ref "S6") (pin "5") (pintype "passive"))
    )
    (net (code "66") (name "Net-(U2-RST)") (class "Default")
      (node (ref "D18") (pin "2") (pintype "passive"))
      (node (ref "D20") (pin "2") (pintype "passive"))
      (node (ref "R29") (pin "2") (pintype "passive"))
      (node (ref "U2") (pin "15") (pinfunction "RST_15") (pintype "passive"))
    )
    (net (code "67") (name "unconnected-(J1-Pad2)") (class "Default")
      (node (ref "J1") (pin "2") (pintype "passive+no_connect"))
    )
    (net (code "68") (name "unconnected-(J2-Pad2)") (class "Default")
      (node (ref "J2") (pin "2") (pintype "passive+no_connect"))
    )
    (net (code "69") (name "unconnected-(J3-Pad2)") (class "Default")
      (node (ref "J3") (pin "2") (pintype "passive+no_connect"))
    )
    (net (code "70") (name "unconnected-(S1-Pad3)") (class "Default")
      (node (ref "S1") (pin "3") (pintype "passive"))
    )
    (net (code "71") (name "unconnected-(S2-Pad3)") (class "Default")
      (node (ref "S2") (pin "3") (pintype "passive"))
    )
    (net (code "72") (name "unconnected-(S3-Pad3)") (class "Default")
      (node (ref "S3") (pin "3") (pintype "passive"))
    )
    (net (code "73") (name "unconnected-(S4-Pad3)") (class "Default")
      (node (ref "S4") (pin "3") (pintype "passive"))
    )
    (net (code "74") (name "unconnected-(S5-Pad3)") (class "Default")
      (node (ref "S5") (pin "3") (pintype "passive"))
    )
    (net (code "75") (name "unconnected-(U2-CARRY-Pad12)") (class "Default")
      (node (ref "U2") (pin "12") (pinfunction "CARRY_12") (pintype "passive+no_connect"))
    )
    (net (code "76") (name "unconnected-(U2-Q6-Pad5)") (class "Default")
      (node (ref "U2") (pin "5") (pinfunction "Q6_5") (pintype "passive+no_connect"))
    )
    (net (code "77") (name "unconnected-(U2-Q7-Pad6)") (class "Default")
      (node (ref "U2") (pin "6") (pinfunction "Q7_6") (pintype "passive+no_connect"))
    )
    (net (code "78") (name "unconnected-(U2-Q8-Pad9)") (class "Default")
      (node (ref "U2") (pin "9") (pinfunction "Q8_9") (pintype "passive+no_connect"))
    )
    (net (code "79") (name "unconnected-(U2-Q9-Pad11)") (class "Default")
      (node (ref "U2") (pin "11") (pinfunction "Q9_11") (pintype "passive+no_connect"))
    )
  )
)
